# US_Driver.net
KiCad netlist of a schematic drawn in Altium Designer
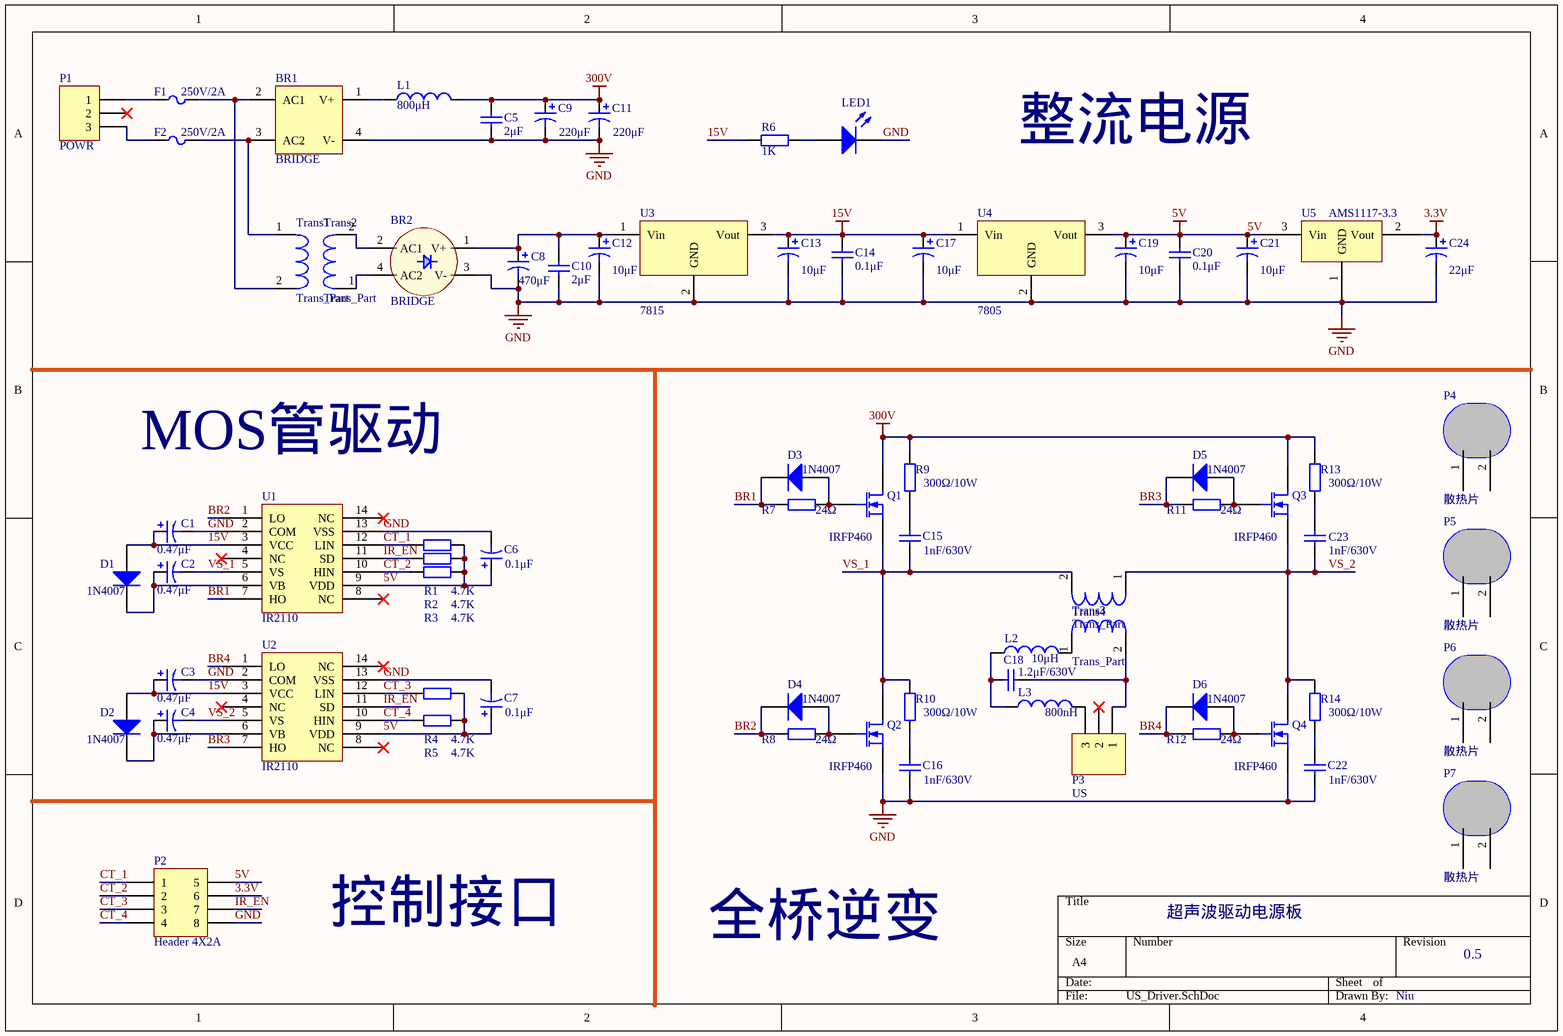
[diagram p0: US_Driver.SchDoc]

(export (version "E")
  (design (tool "Eeschema 10.0.6"))
  (components
    (comp (ref "BR1")
      (value "BRIDGE")
      (footprint "GBU4M")
      (description "BR")
      (libsource (lib "Common") (part "BRIDGE"))
    )
    (comp (ref "BR2")
      (value "BRIDGE")
      (footprint "BR_CIRCLE")
      (description "BR")
      (libsource (lib "Common") (part "BRIDGE_Circle"))
    )
    (comp (ref "C1")
      (value "0.47μF")
      (footprint "Cap_4*7")
      (description "Polarized Capacitor (Surface Mount)")
      (fields (field (name "Comment") "Cap Pol3") (field (name "PUBLISHER") "Altium Limited"))
      (libsource (lib "Miscellaneous Devices") (part "Cap Pol3"))
    )
    (comp (ref "C2")
      (value "0.47μF")
      (footprint "Cap_4*7")
      (description "Polarized Capacitor (Surface Mount)")
      (fields (field (name "Comment") "Cap Pol3") (field (name "PUBLISHER") "Altium Limited"))
      (libsource (lib "Miscellaneous Devices") (part "Cap Pol3"))
    )
    (comp (ref "C3")
      (value "0.47μF")
      (footprint "Cap_4*7")
      (description "Polarized Capacitor (Surface Mount)")
      (fields (field (name "Comment") "Cap Pol3") (field (name "PUBLISHER") "Altium Limited"))
      (libsource (lib "Miscellaneous Devices") (part "Cap Pol3"))
    )
    (comp (ref "C4")
      (value "0.47μF")
      (footprint "Cap_4*7")
      (description "Polarized Capacitor (Surface Mount)")
      (fields (field (name "Comment") "Cap Pol3") (field (name "PUBLISHER") "Altium Limited"))
      (libsource (lib "Miscellaneous Devices") (part "Cap Pol3"))
    )
    (comp (ref "C5")
      (value "2μF")
      (footprint "瓷片电容")
      (description "Capacitor (Semiconductor SIM Model)")
      (fields (field (name "Comment") "Cap Semi") (field (name "PUBLISHER") "Altium Limited"))
      (libsource (lib "Miscellaneous Devices") (part "Cap Semi"))
    )
    (comp (ref "C6")
      (value "0.1μF")
      (footprint "Cap_5*11")
      (description "Polarized Capacitor (Surface Mount)")
      (fields (field (name "Comment") "Cap Pol3") (field (name "PUBLISHER") "Altium Limited"))
      (libsource (lib "Miscellaneous Devices") (part "Cap Pol3"))
    )
    (comp (ref "C7")
      (value "0.1μF")
      (footprint "Cap_5*11")
      (description "Polarized Capacitor (Surface Mount)")
      (fields (field (name "Comment") "Cap Pol3") (field (name "PUBLISHER") "Altium Limited"))
      (libsource (lib "Miscellaneous Devices") (part "Cap Pol3"))
    )
    (comp (ref "C8")
      (value "470μF")
      (footprint "Cap_10*20")
      (description "Polarized Capacitor (Radial)")
      (fields (field (name "Comment") "Cap Pol1") (field (name "PUBLISHER") "Altium Limited"))
      (libsource (lib "Miscellaneous Devices") (part "Cap Pol1"))
    )
    (comp (ref "C9")
      (value "220μF")
      (footprint "Cap_450V")
      (description "Polarized Capacitor (Radial)")
      (fields (field (name "Comment") "Cap Pol1") (field (name "PUBLISHER") "Altium Limited"))
      (libsource (lib "Miscellaneous Devices") (part "Cap Pol1"))
    )
    (comp (ref "C10")
      (value "2μF")
      (footprint "瓷片电容")
      (description "Capacitor (Semiconductor SIM Model)")
      (fields (field (name "Comment") "Cap Semi") (field (name "PUBLISHER") "Altium Limited"))
      (libsource (lib "Miscellaneous Devices") (part "Cap Semi"))
    )
    (comp (ref "C11")
      (value "220μF")
      (footprint "Cap_450V")
      (description "Polarized Capacitor (Radial)")
      (fields (field (name "Comment") "Cap Pol1") (field (name "PUBLISHER") "Altium Limited"))
      (libsource (lib "Miscellaneous Devices") (part "Cap Pol1"))
    )
    (comp (ref "C12")
      (value "10μF")
      (footprint "Cap_5*11")
      (description "Polarized Capacitor (Radial)")
      (fields (field (name "Comment") "Cap Pol1") (field (name "PUBLISHER") "Altium Limited"))
      (libsource (lib "Miscellaneous Devices") (part "Cap Pol1"))
    )
    (comp (ref "C13")
      (value "10μF")
      (footprint "Cap_5*11")
      (description "Polarized Capacitor (Radial)")
      (fields (field (name "Comment") "Cap Pol1") (field (name "PUBLISHER") "Altium Limited"))
      (libsource (lib "Miscellaneous Devices") (part "Cap Pol1"))
    )
    (comp (ref "C14")
      (value "0.1μF")
      (footprint "瓷片电容")
      (description "Capacitor (Semiconductor SIM Model)")
      (fields (field (name "Comment") "Cap Semi") (field (name "PUBLISHER") "Altium Limited"))
      (libsource (lib "Miscellaneous Devices") (part "Cap Semi"))
    )
    (comp (ref "C15")
      (value "1nF/630V")
      (footprint "瓷片电容")
      (description "Capacitor")
      (fields (field (name "Comment") "Cap") (field (name "PUBLISHER") "Altium Limited"))
      (libsource (lib "Miscellaneous Devices") (part "Cap"))
    )
    (comp (ref "C16")
      (value "1nF/630V")
      (footprint "瓷片电容")
      (description "Capacitor")
      (fields (field (name "Comment") "Cap") (field (name "PUBLISHER") "Altium Limited"))
      (libsource (lib "Miscellaneous Devices") (part "Cap"))
    )
    (comp (ref "C17")
      (value "10μF")
      (footprint "Cap_5*11")
      (description "Polarized Capacitor (Radial)")
      (fields (field (name "Comment") "Cap Pol1") (field (name "PUBLISHER") "Altium Limited"))
      (libsource (lib "Miscellaneous Devices") (part "Cap Pol1"))
    )
    (comp (ref "C18")
      (value "1.2μF/630V")
      (footprint "Cap_15")
      (description "Capacitor")
      (fields (field (name "Comment") "Cap") (field (name "PUBLISHER") "Altium Limited"))
      (libsource (lib "Miscellaneous Devices") (part "Cap"))
    )
    (comp (ref "C19")
      (value "10μF")
      (footprint "Cap_5*11")
      (description "Polarized Capacitor (Radial)")
      (fields (field (name "Comment") "Cap Pol1") (field (name "PUBLISHER") "Altium Limited"))
      (libsource (lib "Miscellaneous Devices") (part "Cap Pol1"))
    )
    (comp (ref "C20")
      (value "0.1μF")
      (footprint "瓷片电容")
      (description "Capacitor (Semiconductor SIM Model)")
      (fields (field (name "Comment") "Cap Semi") (field (name "PUBLISHER") "Altium Limited"))
      (libsource (lib "Miscellaneous Devices") (part "Cap Semi"))
    )
    (comp (ref "C21")
      (value "10μF")
      (footprint "Cap_5*11")
      (description "Polarized Capacitor (Radial)")
      (fields (field (name "Comment") "Cap Pol1") (field (name "PUBLISHER") "Altium Limited"))
      (libsource (lib "Miscellaneous Devices") (part "Cap Pol1"))
    )
    (comp (ref "C22")
      (value "1nF/630V")
      (footprint "瓷片电容")
      (description "Capacitor")
      (fields (field (name "Comment") "Cap") (field (name "PUBLISHER") "Altium Limited"))
      (libsource (lib "Miscellaneous Devices") (part "Cap"))
    )
    (comp (ref "C23")
      (value "1nF/630V")
      (footprint "瓷片电容")
      (description "Capacitor")
      (fields (field (name "Comment") "Cap") (field (name "PUBLISHER") "Altium Limited"))
      (libsource (lib "Miscellaneous Devices") (part "Cap"))
    )
    (comp (ref "C24")
      (value "22μF")
      (footprint "Cap_5*11")
      (description "Polarized Capacitor (Radial)")
      (fields (field (name "Comment") "Cap Pol1") (field (name "PUBLISHER") "Altium Limited"))
      (libsource (lib "Miscellaneous Devices") (part "Cap Pol1"))
    )
    (comp (ref "D1")
      (value "1N4007")
      (footprint "DO-41")
      (description "1 Amp General Purpose Rectifier")
      (fields (field (name "PUBLISHER") "Altium Limited"))
      (libsource (lib "Miscellaneous Devices") (part "Diode 1N4007"))
    )
    (comp (ref "D2")
      (value "1N4007")
      (footprint "DO-41")
      (description "1 Amp General Purpose Rectifier")
      (fields (field (name "PUBLISHER") "Altium Limited"))
      (libsource (lib "Miscellaneous Devices") (part "Diode 1N4007"))
    )
    (comp (ref "D3")
      (value "1N4007")
      (footprint "DO-41")
      (description "1 Amp General Purpose Rectifier")
      (fields (field (name "PUBLISHER") "Altium Limited"))
      (libsource (lib "Miscellaneous Devices") (part "Diode 1N4007"))
    )
    (comp (ref "D4")
      (value "1N4007")
      (footprint "DO-41")
      (description "1 Amp General Purpose Rectifier")
      (fields (field (name "PUBLISHER") "Altium Limited"))
      (libsource (lib "Miscellaneous Devices") (part "Diode 1N4007"))
    )
    (comp (ref "D5")
      (value "1N4007")
      (footprint "DO-41")
      (description "1 Amp General Purpose Rectifier")
      (fields (field (name "PUBLISHER") "Altium Limited"))
      (libsource (lib "Miscellaneous Devices") (part "Diode 1N4007"))
    )
    (comp (ref "D6")
      (value "1N4007")
      (footprint "DO-41")
      (description "1 Amp General Purpose Rectifier")
      (fields (field (name "PUBLISHER") "Altium Limited"))
      (libsource (lib "Miscellaneous Devices") (part "Diode 1N4007"))
    )
    (comp (ref "F1")
      (value "250V/2A")
      (footprint "FUSE")
      (description "Fuse")
      (fields (field (name "PUBLISHER") "Altium Limited"))
      (libsource (lib "狗尾巴草设计室") (part "Fuse"))
    )
    (comp (ref "F2")
      (value "250V/2A")
      (footprint "FUSE")
      (description "Fuse")
      (fields (field (name "PUBLISHER") "Altium Limited"))
      (libsource (lib "狗尾巴草设计室") (part "Fuse"))
    )
    (comp (ref "L1")
      (value "800μH")
      (footprint "工字电感8*10")
      (description "Inductor")
      (fields (field (name "PUBLISHER") "Altium Limited"))
      (libsource (lib "Miscellaneous Devices") (part "Inductor"))
    )
    (comp (ref "L2")
      (value "10μH")
      (footprint "工字电感8*10")
      (description "Inductor")
      (fields (field (name "PUBLISHER") "Altium Limited"))
      (libsource (lib "Miscellaneous Devices") (part "Inductor"))
    )
    (comp (ref "L3")
      (value "800nH")
      (footprint "工字电感8*10")
      (description "Inductor")
      (fields (field (name "PUBLISHER") "Altium Limited"))
      (libsource (lib "Miscellaneous Devices") (part "Inductor"))
    )
    (comp (ref "LED1")
      (value "LED1")
      (footprint "BAT-2")
      (description "Typical RED GaAs LED")
      (fields (field (name "PUBLISHER") "Altium Limited"))
      (libsource (lib "Miscellaneous Devices") (part "LED1"))
    )
    (comp (ref "P1")
      (value "POWR")
      (footprint "CH3.96-3P")
      (description "Header, 3-Pin")
      (fields (field (name "PUBLISHER") "Altium Limited"))
      (libsource (lib "Miscellaneous Connectors") (part "Header 3"))
    )
    (comp (ref "P2")
      (value "Header 4X2A")
      (footprint "HDR2X4_CEN")
      (description "Header, 4-Pin, Dual row")
      (fields (field (name "PUBLISHER") "Altium Limited"))
      (libsource (lib "Miscellaneous Connectors") (part "Header 4X2A"))
    )
    (comp (ref "P3")
      (value "US")
      (footprint "CH3.96-3P")
      (description "Header, 3-Pin")
      (fields (field (name "PUBLISHER") "Altium Limited"))
      (libsource (lib "Miscellaneous Connectors") (part "Header 3"))
    )
    (comp (ref "P4") (value "散热片") (footprint "散热器_TO247") (libsource (lib "Common") (part "散热片")))
    (comp (ref "P5") (value "散热片") (footprint "散热器_TO247") (libsource (lib "Common") (part "散热片")))
    (comp (ref "P6") (value "散热片") (footprint "散热器_TO247") (libsource (lib "Common") (part "散热片")))
    (comp (ref "P7") (value "散热片") (footprint "散热器_TO247") (libsource (lib "Common") (part "散热片")))
    (comp (ref "Q1")
      (value "IRFP460")
      (footprint "TO-247")
      (description "N-Channel MOSFET")
      (fields (field (name "Comment") "MOSFET-N") (field (name "PUBLISHER") "Altium Limited"))
      (libsource (lib "Miscellaneous Devices") (part "MOSFET-N"))
    )
    (comp (ref "Q2")
      (value "IRFP460")
      (footprint "TO-247")
      (description "N-Channel MOSFET")
      (fields (field (name "Comment") "MOSFET-N") (field (name "PUBLISHER") "Altium Limited"))
      (libsource (lib "Miscellaneous Devices") (part "MOSFET-N"))
    )
    (comp (ref "Q3")
      (value "IRFP460")
      (footprint "TO-247")
      (description "N-Channel MOSFET")
      (fields (field (name "Comment") "MOSFET-N") (field (name "PUBLISHER") "Altium Limited"))
      (libsource (lib "Miscellaneous Devices") (part "MOSFET-N"))
    )
    (comp (ref "Q4")
      (value "IRFP460")
      (footprint "TO-247")
      (description "N-Channel MOSFET")
      (fields (field (name "Comment") "MOSFET-N") (field (name "PUBLISHER") "Altium Limited"))
      (libsource (lib "Miscellaneous Devices") (part "MOSFET-N"))
    )
    (comp (ref "R1")
      (value "4.7K")
      (footprint "AXIAL-0.4")
      (description "Resistor")
      (fields (field (name "Comment") "Res2") (field (name "PUBLISHER") "Altium Limited"))
      (libsource (lib "Miscellaneous Devices") (part "Res2"))
    )
    (comp (ref "R2")
      (value "4.7K")
      (footprint "AXIAL-0.4")
      (description "Resistor")
      (fields (field (name "Comment") "Res2") (field (name "PUBLISHER") "Altium Limited"))
      (libsource (lib "Miscellaneous Devices") (part "Res2"))
    )
    (comp (ref "R3")
      (value "4.7K")
      (footprint "AXIAL-0.4")
      (description "Resistor")
      (fields (field (name "Comment") "Res2") (field (name "PUBLISHER") "Altium Limited"))
      (libsource (lib "Miscellaneous Devices") (part "Res2"))
    )
    (comp (ref "R4")
      (value "4.7K")
      (footprint "AXIAL-0.4")
      (description "Resistor")
      (fields (field (name "Comment") "Res2") (field (name "PUBLISHER") "Altium Limited"))
      (libsource (lib "Miscellaneous Devices") (part "Res2"))
    )
    (comp (ref "R5")
      (value "4.7K")
      (footprint "AXIAL-0.4")
      (description "Resistor")
      (fields (field (name "Comment") "Res2") (field (name "PUBLISHER") "Altium Limited"))
      (libsource (lib "Miscellaneous Devices") (part "Res2"))
    )
    (comp (ref "R6")
      (value "1K")
      (footprint "AXIAL-0.4")
      (description "Resistor")
      (fields (field (name "Comment") "Res2") (field (name "PUBLISHER") "Altium Limited"))
      (libsource (lib "") (part "Res2_1"))
    )
    (comp (ref "R7")
      (value "24Ω")
      (footprint "AXIAL-0.4")
      (description "Resistor")
      (fields (field (name "Comment") "Res2") (field (name "PUBLISHER") "Altium Limited"))
      (libsource (lib "Miscellaneous Devices") (part "Res2"))
    )
    (comp (ref "R8")
      (value "24Ω")
      (footprint "AXIAL-0.4")
      (description "Resistor")
      (fields (field (name "Comment") "Res2") (field (name "PUBLISHER") "Altium Limited"))
      (libsource (lib "Miscellaneous Devices") (part "Res2"))
    )
    (comp (ref "R9")
      (value "300Ω/10W")
      (footprint "Res_10W_立式")
      (description "Resistor")
      (fields (field (name "Comment") "Res2") (field (name "PUBLISHER") "Altium Limited"))
      (libsource (lib "") (part "Res2_2"))
    )
    (comp (ref "R10")
      (value "300Ω/10W")
      (footprint "Res_10W_立式")
      (description "Resistor")
      (fields (field (name "Comment") "Res2") (field (name "PUBLISHER") "Altium Limited"))
      (libsource (lib "") (part "Res2_2"))
    )
    (comp (ref "R11")
      (value "24Ω")
      (footprint "AXIAL-0.4")
      (description "Resistor")
      (fields (field (name "Comment") "Res2") (field (name "PUBLISHER") "Altium Limited"))
      (libsource (lib "Miscellaneous Devices") (part "Res2"))
    )
    (comp (ref "R12")
      (value "24Ω")
      (footprint "AXIAL-0.4")
      (description "Resistor")
      (fields (field (name "Comment") "Res2") (field (name "PUBLISHER") "Altium Limited"))
      (libsource (lib "Miscellaneous Devices") (part "Res2"))
    )
    (comp (ref "R13")
      (value "300Ω/10W")
      (footprint "Res_10W_立式")
      (description "Resistor")
      (fields (field (name "Comment") "Res2") (field (name "PUBLISHER") "Altium Limited"))
      (libsource (lib "") (part "Res2_2"))
    )
    (comp (ref "R14")
      (value "300Ω/10W")
      (footprint "Res_10W_立式")
      (description "Resistor")
      (fields (field (name "Comment") "Res2") (field (name "PUBLISHER") "Altium Limited"))
      (libsource (lib "") (part "Res2_2"))
    )
    (comp (ref "Trans1")
      (value "Trans_Part")
      (footprint "Trans_Part")
      (libsource (lib "") (part "Trans_Part_1"))
    )
    (comp (ref "Trans2")
      (value "Trans_Part")
      (footprint "Trans_Part")
      (libsource (lib "") (part "Trans_Part_1"))
    )
    (comp (ref "Trans3")
      (value "Trans_Part")
      (footprint "Trans_Part")
      (libsource (lib "Common") (part "Trans_Part"))
    )
    (comp (ref "Trans4")
      (value "Trans_Part")
      (footprint "Trans_Part")
      (libsource (lib "Common") (part "Trans_Part"))
    )
    (comp (ref "U1") (value "IR2110") (footprint "DIP-14") (libsource (lib "Common") (part "IR2110")))
    (comp (ref "U2") (value "IR2110") (footprint "DIP-14") (libsource (lib "Common") (part "IR2110")))
    (comp (ref "U3") (value "7815") (footprint "TO-220AB") (libsource (lib "Schlib2") (part "7805")))
    (comp (ref "U4") (value "7805") (footprint "TO-220AB") (libsource (lib "Schlib2") (part "7805")))
    (comp (ref "U5")
      (value "AMS1117-3.3")
      (footprint "TO-220AB")
      (libsource (lib "Common") (part "AMS1117-3.3"))
    )
  )
  (nets
    (net (code "1") (name "/BR1") (class "Default")
      (node (ref "D3") (pin "2") (pinfunction "K_2") (pintype "passive"))
      (node (ref "R7") (pin "1") (pinfunction "1_1") (pintype "passive"))
      (node (ref "U1") (pin "7") (pinfunction "HO_7") (pintype "passive"))
    )
    (net (code "2") (name "/BR2") (class "Default")
      (node (ref "D4") (pin "2") (pinfunction "K_2") (pintype "passive"))
      (node (ref "R8") (pin "1") (pinfunction "1_1") (pintype "passive"))
      (node (ref "U1") (pin "1") (pinfunction "LO_1") (pintype "passive"))
    )
    (net (code "3") (name "/BR3") (class "Default")
      (node (ref "D5") (pin "2") (pinfunction "K_2") (pintype "passive"))
      (node (ref "R11") (pin "1") (pinfunction "1_1") (pintype "passive"))
      (node (ref "U2") (pin "7") (pinfunction "HO_7") (pintype "passive"))
    )
    (net (code "4") (name "/BR4") (class "Default")
      (node (ref "D6") (pin "2") (pinfunction "K_2") (pintype "passive"))
      (node (ref "R12") (pin "1") (pinfunction "1_1") (pintype "passive"))
      (node (ref "U2") (pin "1") (pinfunction "LO_1") (pintype "passive"))
    )
    (net (code "5") (name "/CT_1") (class "Default")
      (node (ref "P2") (pin "1") (pinfunction "1_1") (pintype "passive"))
      (node (ref "R1") (pin "1") (pinfunction "1_1") (pintype "passive"))
      (node (ref "U1") (pin "12") (pinfunction "LIN_12") (pintype "passive"))
    )
    (net (code "6") (name "/CT_2") (class "Default")
      (node (ref "P2") (pin "2") (pinfunction "2_2") (pintype "passive"))
      (node (ref "R3") (pin "1") (pinfunction "1_1") (pintype "passive"))
      (node (ref "U1") (pin "10") (pinfunction "HIN_10") (pintype "passive"))
    )
    (net (code "7") (name "/CT_3") (class "Default")
      (node (ref "P2") (pin "3") (pinfunction "3_3") (pintype "passive"))
      (node (ref "R4") (pin "1") (pinfunction "1_1") (pintype "passive"))
      (node (ref "U2") (pin "12") (pinfunction "LIN_12") (pintype "passive"))
    )
    (net (code "8") (name "/CT_4") (class "Default")
      (node (ref "P2") (pin "4") (pinfunction "4_4") (pintype "passive"))
      (node (ref "R5") (pin "1") (pinfunction "1_1") (pintype "passive"))
      (node (ref "U2") (pin "10") (pinfunction "HIN_10") (pintype "passive"))
    )
    (net (code "9") (name "/IR_EN") (class "Default")
      (node (ref "P2") (pin "7") (pinfunction "7_7") (pintype "passive"))
      (node (ref "R2") (pin "1") (pinfunction "1_1") (pintype "passive"))
      (node (ref "U1") (pin "11") (pinfunction "SD_11") (pintype "passive"))
      (node (ref "U2") (pin "11") (pinfunction "SD_11") (pintype "passive"))
    )
    (net (code "10") (name "/VS_1") (class "Default")
      (node (ref "C15") (pin "1") (pinfunction "1_1") (pintype "passive"))
      (node (ref "C2") (pin "2") (pinfunction "2_2") (pintype "passive"))
      (node (ref "Q1") (pin "3") (pinfunction "S_3") (pintype "passive"))
      (node (ref "Q2") (pin "1") (pinfunction "D_1") (pintype "passive"))
      (node (ref "R10") (pin "2") (pinfunction "2_2") (pintype "passive"))
      (node (ref "Trans3") (pin "2") (pinfunction "2_2") (pintype "passive"))
      (node (ref "U1") (pin "5") (pinfunction "VS_5") (pintype "passive"))
    )
    (net (code "11") (name "/VS_2") (class "Default")
      (node (ref "C23") (pin "1") (pinfunction "1_1") (pintype "passive"))
      (node (ref "C4") (pin "2") (pinfunction "2_2") (pintype "passive"))
      (node (ref "Q3") (pin "3") (pinfunction "S_3") (pintype "passive"))
      (node (ref "Q4") (pin "1") (pinfunction "D_1") (pintype "passive"))
      (node (ref "R14") (pin "2") (pinfunction "2_2") (pintype "passive"))
      (node (ref "Trans3") (pin "1") (pinfunction "1_1") (pintype "passive"))
      (node (ref "U2") (pin "5") (pinfunction "VS_5") (pintype "passive"))
    )
    (net (code "12") (name "3.3V") (class "Default")
      (node (ref "C24") (pin "1") (pinfunction "1_1") (pintype "passive"))
      (node (ref "P2") (pin "6") (pinfunction "6_6") (pintype "passive"))
      (node (ref "U5") (pin "2") (pinfunction "Vout_2") (pintype "passive"))
    )
    (net (code "13") (name "5V") (class "Default")
      (node (ref "C19") (pin "1") (pinfunction "1_1") (pintype "passive"))
      (node (ref "C20") (pin "2") (pinfunction "2_2") (pintype "passive"))
      (node (ref "C21") (pin "1") (pinfunction "1_1") (pintype "passive"))
      (node (ref "C6") (pin "1") (pinfunction "1_1") (pintype "passive"))
      (node (ref "C7") (pin "1") (pinfunction "1_1") (pintype "passive"))
      (node (ref "P2") (pin "5") (pinfunction "5_5") (pintype "passive"))
      (node (ref "R1") (pin "2") (pinfunction "2_2") (pintype "passive"))
      (node (ref "R2") (pin "2") (pinfunction "2_2") (pintype "passive"))
      (node (ref "R3") (pin "2") (pinfunction "2_2") (pintype "passive"))
      (node (ref "R4") (pin "2") (pinfunction "2_2") (pintype "passive"))
      (node (ref "R5") (pin "2") (pinfunction "2_2") (pintype "passive"))
      (node (ref "U1") (pin "9") (pinfunction "VDD_9") (pintype "passive"))
      (node (ref "U2") (pin "9") (pinfunction "VDD_9") (pintype "passive"))
      (node (ref "U4") (pin "3") (pinfunction "Vout_3") (pintype "passive"))
      (node (ref "U5") (pin "3") (pinfunction "Vin_3") (pintype "passive"))
    )
    (net (code "14") (name "15V") (class "Default")
      (node (ref "C1") (pin "1") (pinfunction "1_1") (pintype "passive"))
      (node (ref "C13") (pin "1") (pinfunction "1_1") (pintype "passive"))
      (node (ref "C14") (pin "2") (pinfunction "2_2") (pintype "passive"))
      (node (ref "C17") (pin "1") (pinfunction "1_1") (pintype "passive"))
      (node (ref "C3") (pin "1") (pinfunction "1_1") (pintype "passive"))
      (node (ref "D1") (pin "1") (pinfunction "A_1") (pintype "passive"))
      (node (ref "D2") (pin "1") (pinfunction "A_1") (pintype "passive"))
      (node (ref "R6") (pin "2") (pinfunction "2_2") (pintype "passive"))
      (node (ref "U1") (pin "3") (pinfunction "VCC_3") (pintype "passive"))
      (node (ref "U2") (pin "3") (pinfunction "VCC_3") (pintype "passive"))
      (node (ref "U3") (pin "3") (pinfunction "Vout_3") (pintype "passive"))
      (node (ref "U4") (pin "1") (pinfunction "Vin_1") (pintype "passive"))
    )
    (net (code "15") (name "300V") (class "Default")
      (node (ref "C11") (pin "1") (pinfunction "1_1") (pintype "passive"))
      (node (ref "C5") (pin "2") (pinfunction "2_2") (pintype "passive"))
      (node (ref "C9") (pin "1") (pinfunction "1_1") (pintype "passive"))
      (node (ref "L1") (pin "2") (pinfunction "2_2") (pintype "passive"))
      (node (ref "Q1") (pin "1") (pinfunction "D_1") (pintype "passive"))
      (node (ref "Q3") (pin "1") (pinfunction "D_1") (pintype "passive"))
      (node (ref "R13") (pin "2") (pinfunction "2_2") (pintype "passive"))
      (node (ref "R9") (pin "2") (pinfunction "2_2") (pintype "passive"))
    )
    (net (code "16") (name "GND") (class "Default")
      (node (ref "BR1") (pin "4") (pinfunction "V-_4") (pintype "passive"))
      (node (ref "BR2") (pin "3") (pinfunction "V-_3") (pintype "passive"))
      (node (ref "C1") (pin "2") (pinfunction "2_2") (pintype "passive"))
      (node (ref "C10") (pin "1") (pinfunction "1_1") (pintype "passive"))
      (node (ref "C11") (pin "2") (pinfunction "2_2") (pintype "passive"))
      (node (ref "C12") (pin "2") (pinfunction "2_2") (pintype "passive"))
      (node (ref "C13") (pin "2") (pinfunction "2_2") (pintype "passive"))
      (node (ref "C14") (pin "1") (pinfunction "1_1") (pintype "passive"))
      (node (ref "C16") (pin "1") (pinfunction "1_1") (pintype "passive"))
      (node (ref "C17") (pin "2") (pinfunction "2_2") (pintype "passive"))
      (node (ref "C19") (pin "2") (pinfunction "2_2") (pintype "passive"))
      (node (ref "C20") (pin "1") (pinfunction "1_1") (pintype "passive"))
      (node (ref "C21") (pin "2") (pinfunction "2_2") (pintype "passive"))
      (node (ref "C22") (pin "1") (pinfunction "1_1") (pintype "passive"))
      (node (ref "C24") (pin "2") (pinfunction "2_2") (pintype "passive"))
      (node (ref "C3") (pin "2") (pinfunction "2_2") (pintype "passive"))
      (node (ref "C5") (pin "1") (pinfunction "1_1") (pintype "passive"))
      (node (ref "C6") (pin "2") (pinfunction "2_2") (pintype "passive"))
      (node (ref "C7") (pin "2") (pinfunction "2_2") (pintype "passive"))
      (node (ref "C8") (pin "2") (pinfunction "2_2") (pintype "passive"))
      (node (ref "C9") (pin "2") (pinfunction "2_2") (pintype "passive"))
      (node (ref "LED1") (pin "2") (pinfunction "K_2") (pintype "passive"))
      (node (ref "P2") (pin "8") (pinfunction "8_8") (pintype "passive"))
      (node (ref "Q2") (pin "3") (pinfunction "S_3") (pintype "passive"))
      (node (ref "Q4") (pin "3") (pinfunction "S_3") (pintype "passive"))
      (node (ref "U1") (pin "13") (pinfunction "VSS_13") (pintype "passive"))
      (node (ref "U1") (pin "2") (pinfunction "COM_2") (pintype "passive"))
      (node (ref "U2") (pin "13") (pinfunction "VSS_13") (pintype "passive"))
      (node (ref "U2") (pin "2") (pinfunction "COM_2") (pintype "passive"))
      (node (ref "U3") (pin "2") (pinfunction "GND_2") (pintype "passive"))
      (node (ref "U4") (pin "2") (pinfunction "GND_2") (pintype "passive"))
      (node (ref "U5") (pin "1") (pinfunction "GND_1") (pintype "passive"))
    )
    (net (code "17") (name "Net-(BR1-AC1)") (class "Default")
      (node (ref "BR1") (pin "2") (pinfunction "AC1_2") (pintype "passive"))
      (node (ref "F1") (pin "2") (pinfunction "2_2") (pintype "passive"))
      (node (ref "Trans1") (pin "2") (pinfunction "2_2") (pintype "passive"))
    )
    (net (code "18") (name "Net-(BR1-AC2)") (class "Default")
      (node (ref "BR1") (pin "3") (pinfunction "AC2_3") (pintype "passive"))
      (node (ref "F2") (pin "2") (pinfunction "2_2") (pintype "passive"))
      (node (ref "Trans1") (pin "1") (pinfunction "1_1") (pintype "passive"))
    )
    (net (code "19") (name "Net-(BR1-V+)") (class "Default")
      (node (ref "BR1") (pin "1") (pinfunction "V+_1") (pintype "passive"))
      (node (ref "L1") (pin "1") (pinfunction "1_1") (pintype "passive"))
    )
    (net (code "20") (name "Net-(BR2-AC1)") (class "Default")
      (node (ref "BR2") (pin "2") (pinfunction "AC1_2") (pintype "passive"))
      (node (ref "Trans2") (pin "2") (pinfunction "2_2") (pintype "passive"))
    )
    (net (code "21") (name "Net-(BR2-AC2)") (class "Default")
      (node (ref "BR2") (pin "4") (pinfunction "AC2_4") (pintype "passive"))
      (node (ref "Trans2") (pin "1") (pinfunction "1_1") (pintype "passive"))
    )
    (net (code "22") (name "Net-(BR2-V+)") (class "Default")
      (node (ref "BR2") (pin "1") (pinfunction "V+_1") (pintype "passive"))
      (node (ref "C10") (pin "2") (pinfunction "2_2") (pintype "passive"))
      (node (ref "C12") (pin "1") (pinfunction "1_1") (pintype "passive"))
      (node (ref "C8") (pin "1") (pinfunction "1_1") (pintype "passive"))
      (node (ref "U3") (pin "1") (pinfunction "Vin_1") (pintype "passive"))
    )
    (net (code "23") (name "Net-(C15-Pad2)") (class "Default")
      (node (ref "C15") (pin "2") (pinfunction "2_2") (pintype "passive"))
      (node (ref "R9") (pin "1") (pinfunction "1_1") (pintype "passive"))
    )
    (net (code "24") (name "Net-(C16-Pad2)") (class "Default")
      (node (ref "C16") (pin "2") (pinfunction "2_2") (pintype "passive"))
      (node (ref "R10") (pin "1") (pinfunction "1_1") (pintype "passive"))
    )
    (net (code "25") (name "Net-(C18-Pad1)") (class "Default")
      (node (ref "C18") (pin "1") (pinfunction "1_1") (pintype "passive"))
      (node (ref "P3") (pin "1") (pinfunction "1_1") (pintype "passive"))
      (node (ref "Trans4") (pin "2") (pinfunction "2_2") (pintype "passive"))
    )
    (net (code "26") (name "Net-(C18-Pad2)") (class "Default")
      (node (ref "C18") (pin "2") (pinfunction "2_2") (pintype "passive"))
      (node (ref "L2") (pin "1") (pinfunction "1_1") (pintype "passive"))
      (node (ref "L3") (pin "1") (pinfunction "1_1") (pintype "passive"))
    )
    (net (code "27") (name "Net-(C22-Pad2)") (class "Default")
      (node (ref "C22") (pin "2") (pinfunction "2_2") (pintype "passive"))
      (node (ref "R14") (pin "1") (pinfunction "1_1") (pintype "passive"))
    )
    (net (code "28") (name "Net-(C23-Pad2)") (class "Default")
      (node (ref "C23") (pin "2") (pinfunction "2_2") (pintype "passive"))
      (node (ref "R13") (pin "1") (pinfunction "1_1") (pintype "passive"))
    )
    (net (code "29") (name "Net-(D1-K)") (class "Default")
      (node (ref "C2") (pin "1") (pinfunction "1_1") (pintype "passive"))
      (node (ref "D1") (pin "2") (pinfunction "K_2") (pintype "passive"))
      (node (ref "U1") (pin "6") (pinfunction "VB_6") (pintype "passive"))
    )
    (net (code "30") (name "Net-(D2-K)") (class "Default")
      (node (ref "C4") (pin "1") (pinfunction "1_1") (pintype "passive"))
      (node (ref "D2") (pin "2") (pinfunction "K_2") (pintype "passive"))
      (node (ref "U2") (pin "6") (pinfunction "VB_6") (pintype "passive"))
    )
    (net (code "31") (name "Net-(D3-A)") (class "Default")
      (node (ref "D3") (pin "1") (pinfunction "A_1") (pintype "passive"))
      (node (ref "Q1") (pin "2") (pinfunction "G_2") (pintype "passive"))
      (node (ref "R7") (pin "2") (pinfunction "2_2") (pintype "passive"))
    )
    (net (code "32") (name "Net-(D4-A)") (class "Default")
      (node (ref "D4") (pin "1") (pinfunction "A_1") (pintype "passive"))
      (node (ref "Q2") (pin "2") (pinfunction "G_2") (pintype "passive"))
      (node (ref "R8") (pin "2") (pinfunction "2_2") (pintype "passive"))
    )
    (net (code "33") (name "Net-(D5-A)") (class "Default")
      (node (ref "D5") (pin "1") (pinfunction "A_1") (pintype "passive"))
      (node (ref "Q3") (pin "2") (pinfunction "G_2") (pintype "passive"))
      (node (ref "R11") (pin "2") (pinfunction "2_2") (pintype "passive"))
    )
    (net (code "34") (name "Net-(D6-A)") (class "Default")
      (node (ref "D6") (pin "1") (pinfunction "A_1") (pintype "passive"))
      (node (ref "Q4") (pin "2") (pinfunction "G_2") (pintype "passive"))
      (node (ref "R12") (pin "2") (pinfunction "2_2") (pintype "passive"))
    )
    (net (code "35") (name "Net-(F1-Pad1)") (class "Default")
      (node (ref "F1") (pin "1") (pinfunction "1_1") (pintype "passive"))
      (node (ref "P1") (pin "1") (pinfunction "1_1") (pintype "passive"))
    )
    (net (code "36") (name "Net-(F2-Pad1)") (class "Default")
      (node (ref "F2") (pin "1") (pinfunction "1_1") (pintype "passive"))
      (node (ref "P1") (pin "3") (pinfunction "3_3") (pintype "passive"))
    )
    (net (code "37") (name "Net-(L2-Pad2)") (class "Default")
      (node (ref "L2") (pin "2") (pinfunction "2_2") (pintype "passive"))
      (node (ref "Trans4") (pin "1") (pinfunction "1_1") (pintype "passive"))
    )
    (net (code "38") (name "Net-(L3-Pad2)") (class "Default")
      (node (ref "L3") (pin "2") (pinfunction "2_2") (pintype "passive"))
      (node (ref "P3") (pin "3") (pinfunction "3_3") (pintype "passive"))
    )
    (net (code "39") (name "Net-(LED1-A)") (class "Default")
      (node (ref "LED1") (pin "1") (pinfunction "A_1") (pintype "passive"))
      (node (ref "R6") (pin "1") (pinfunction "1_1") (pintype "passive"))
    )
    (net (code "40") (name "unconnected-(P1-Pad2)") (class "Default")
      (node (ref "P1") (pin "2") (pinfunction "2_2") (pintype "passive+no_connect"))
    )
    (net (code "41") (name "unconnected-(P3-Pad2)") (class "Default")
      (node (ref "P3") (pin "2") (pinfunction "2_2") (pintype "passive+no_connect"))
    )
    (net (code "42") (name "unconnected-(P4-Pad1)") (class "Default")
      (node (ref "P4") (pin "1") (pinfunction "1_1") (pintype "passive"))
    )
    (net (code "43") (name "unconnected-(P4-Pad2)") (class "Default")
      (node (ref "P4") (pin "2") (pinfunction "2_2") (pintype "passive"))
    )
    (net (code "44") (name "unconnected-(P5-Pad1)") (class "Default")
      (node (ref "P5") (pin "1") (pinfunction "1_1") (pintype "passive"))
    )
    (net (code "45") (name "unconnected-(P5-Pad2)") (class "Default")
      (node (ref "P5") (pin "2") (pinfunction "2_2") (pintype "passive"))
    )
    (net (code "46") (name "unconnected-(P6-Pad1)") (class "Default")
      (node (ref "P6") (pin "1") (pinfunction "1_1") (pintype "passive"))
    )
    (net (code "47") (name "unconnected-(P6-Pad2)") (class "Default")
      (node (ref "P6") (pin "2") (pinfunction "2_2") (pintype "passive"))
    )
    (net (code "48") (name "unconnected-(P7-Pad1)") (class "Default")
      (node (ref "P7") (pin "1") (pinfunction "1_1") (pintype "passive"))
    )
    (net (code "49") (name "unconnected-(P7-Pad2)") (class "Default")
      (node (ref "P7") (pin "2") (pinfunction "2_2") (pintype "passive"))
    )
    (net (code "50") (name "unconnected-(U1-NC-Pad4)") (class "Default")
      (node (ref "U1") (pin "4") (pinfunction "NC_4") (pintype "passive+no_connect"))
    )
    (net (code "51") (name "unconnected-(U1-NC-Pad8)") (class "Default")
      (node (ref "U1") (pin "8") (pinfunction "NC_8") (pintype "passive+no_connect"))
    )
    (net (code "52") (name "unconnected-(U1-NC-Pad14)") (class "Default")
      (node (ref "U1") (pin "14") (pinfunction "NC_14") (pintype "passive+no_connect"))
    )
    (net (code "53") (name "unconnected-(U2-NC-Pad4)") (class "Default")
      (node (ref "U2") (pin "4") (pinfunction "NC_4") (pintype "passive+no_connect"))
    )
    (net (code "54") (name "unconnected-(U2-NC-Pad8)") (class "Default")
      (node (ref "U2") (pin "8") (pinfunction "NC_8") (pintype "passive+no_connect"))
    )
    (net (code "55") (name "unconnected-(U2-NC-Pad14)") (class "Default")
      (node (ref "U2") (pin "14") (pinfunction "NC_14") (pintype "passive+no_connect"))
    )
  )
)
